# Ivy_Sensor_Shield.net
KiCad netlist of a schematic drawn in EAGLE
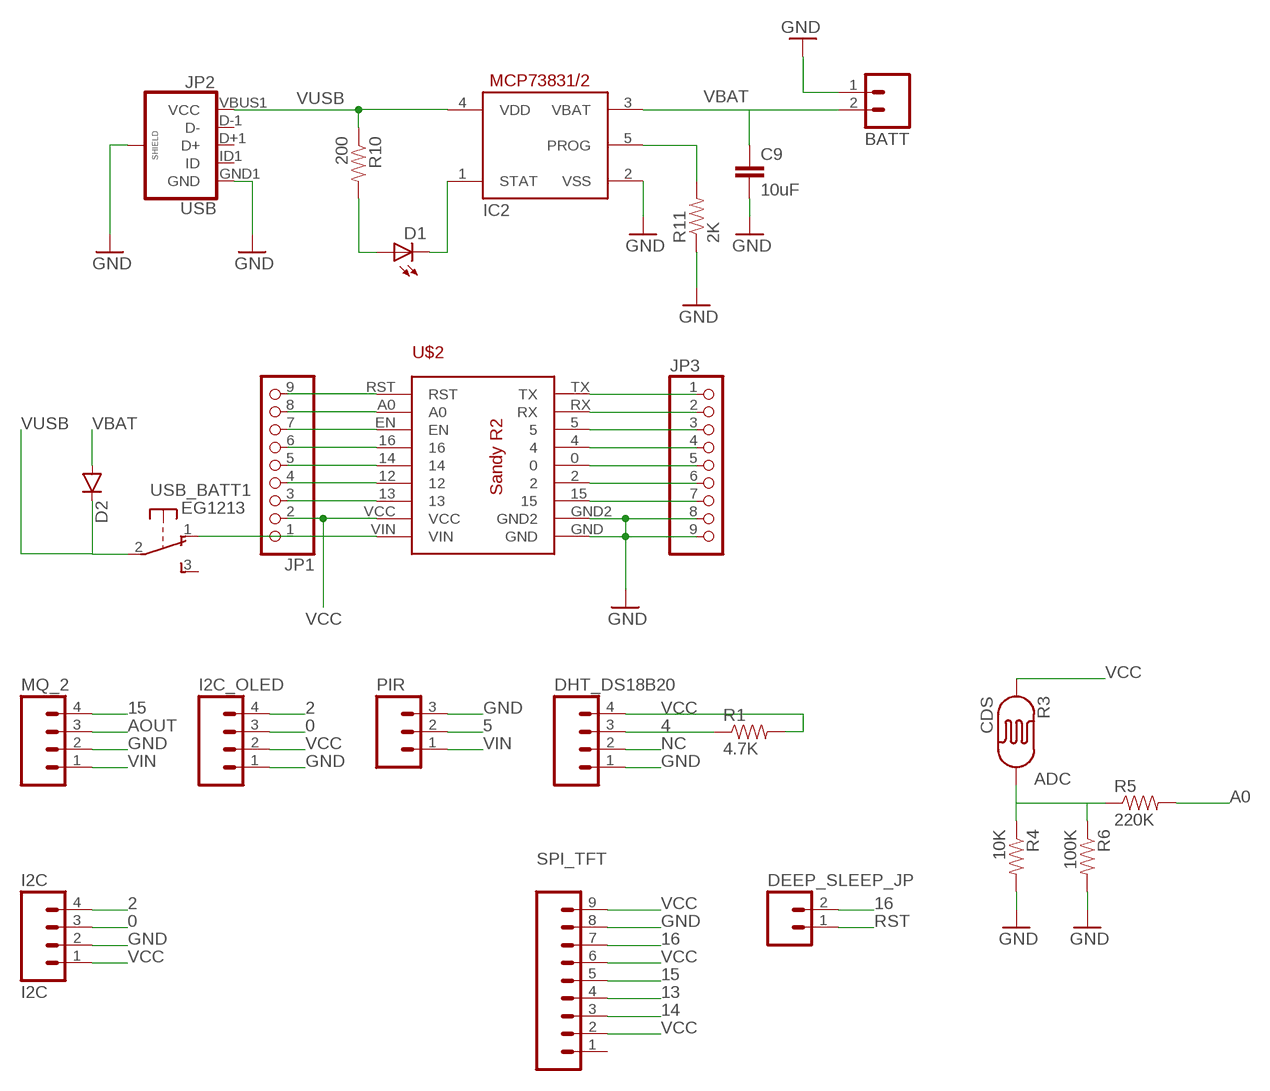
[diagram p0: schematic, sheet 1]

(export (version "E")
  (design (tool "Eeschema 10.0.6"))
  (components
    (comp (ref "BATT")
      (value "M02PTH")
      (footprint "eagle-import:1X02")
      (libsource (lib "eagle-import") (part "M02PTH"))
    )
    (comp (ref "C9")
      (value "10uF")
      (footprint "eagle-import:0805")
      (libsource (lib "eagle-import") (part "CAP0805"))
    )
    (comp (ref "D1")
      (value "LEDCHIPLED_0805")
      (footprint "eagle-import:CHIPLED_0805")
      (libsource (lib "eagle-import") (part "LEDCHIPLED_0805"))
    )
    (comp (ref "D2")
      (value "DIODESOD123")
      (footprint "eagle-import:SOD-123")
      (libsource (lib "eagle-import") (part "DIODESOD123"))
    )
    (comp (ref "DEEP_SLEEP_JP")
      (value "M02PTH")
      (footprint "eagle-import:1X02")
      (libsource (lib "eagle-import") (part "M02PTH"))
    )
    (comp (ref "DHT_DS18B20")
      (value "M04PTH")
      (footprint "eagle-import:1X04")
      (libsource (lib "eagle-import") (part "M04PTH"))
    )
    (comp (ref "I2C")
      (value "I2C")
      (footprint "eagle-import:1X04")
      (libsource (lib "eagle-import") (part "M04PTH"))
    )
    (comp (ref "I2C_OLED")
      (value "M04PTH")
      (footprint "eagle-import:1X04")
      (libsource (lib "eagle-import") (part "M04PTH"))
    )
    (comp (ref "IC2")
      (value "MCP73831/OT")
      (footprint "eagle-import:SOT23-5L")
      (libsource (lib "eagle-import") (part "MCP73831/OT"))
    )
    (comp (ref "JP1")
      (value "PINHD-1X9")
      (footprint "eagle-import:1X09-BIG")
      (libsource (lib "eagle-import") (part "PINHD-1X9"))
    )
    (comp (ref "JP2")
      (value "USB")
      (footprint "eagle-import:USB-B-MICRO-SMD_V03")
      (libsource (lib "eagle-import") (part "USB_MICROB_PLUGCONN-11752"))
    )
    (comp (ref "JP3")
      (value "PINHD-1X9")
      (footprint "eagle-import:1X09-BIG")
      (libsource (lib "eagle-import") (part "PINHD-1X9"))
    )
    (comp (ref "MQ_2")
      (value "M04PTH")
      (footprint "eagle-import:1X04")
      (libsource (lib "eagle-import") (part "M04PTH"))
    )
    (comp (ref "PIR")
      (value "M03PTH")
      (footprint "eagle-import:1X03")
      (libsource (lib "eagle-import") (part "M03PTH"))
    )
    (comp (ref "R1")
      (value "4.7K")
      (footprint "eagle-import:0805")
      (libsource (lib "eagle-import") (part "RESISTOR0805-RES"))
    )
    (comp (ref "R3")
      (value "CDS")
      (footprint "eagle-import:PHOTOCELL_THIN")
      (libsource (lib "eagle-import") (part "PHOTOCELL"))
    )
    (comp (ref "R4")
      (value "10K")
      (footprint "eagle-import:0805")
      (libsource (lib "eagle-import") (part "RESISTOR0805-RES"))
    )
    (comp (ref "R5")
      (value "220K")
      (footprint "eagle-import:0805")
      (libsource (lib "eagle-import") (part "RESISTOR0805-RES"))
    )
    (comp (ref "R6")
      (value "100K")
      (footprint "eagle-import:0805")
      (libsource (lib "eagle-import") (part "RESISTOR0805-RES"))
    )
    (comp (ref "R10")
      (value "200")
      (footprint "eagle-import:0805")
      (libsource (lib "eagle-import") (part "RESISTOR0805-RES"))
    )
    (comp (ref "R11")
      (value "2K")
      (footprint "eagle-import:0805")
      (libsource (lib "eagle-import") (part "RESISTOR0805-RES"))
    )
    (comp (ref "SPI_TFT")
      (value "M09")
      (footprint "eagle-import:1X09")
      (libsource (lib "eagle-import") (part "M09"))
    )
    (comp (ref "U$2")
      (value "MINI-ESPMINI-ESP-LOCK")
      (footprint "eagle-import:MINI-ESP-LOCK")
      (libsource (lib "eagle-import") (part "MINI-ESPMINI-ESP-LOCK"))
    )
    (comp (ref "USB_BATT")
      (value "EG1213")
      (footprint "eagle-import:EG1213")
      (libsource (lib "eagle-import") (part "EG1213"))
    )
  )
  (nets
    (net (code "1") (name "/0") (class "Default")
      (node (ref "I2C") (pin "3") (pinfunction "3_3") (pintype "passive"))
      (node (ref "I2C_OLED") (pin "3") (pinfunction "3_3") (pintype "passive"))
      (node (ref "JP3") (pin "5") (pinfunction "5_5") (pintype "passive"))
      (node (ref "U$2") (pin "0") (pinfunction "0_0") (pintype "bidirectional"))
    )
    (net (code "2") (name "/2") (class "Default")
      (node (ref "I2C") (pin "4") (pinfunction "4_4") (pintype "passive"))
      (node (ref "I2C_OLED") (pin "4") (pinfunction "4_4") (pintype "passive"))
      (node (ref "JP3") (pin "6") (pinfunction "6_6") (pintype "passive"))
      (node (ref "U$2") (pin "2") (pinfunction "2_2") (pintype "bidirectional"))
    )
    (net (code "3") (name "/4") (class "Default")
      (node (ref "DHT_DS18B20") (pin "3") (pinfunction "3_3") (pintype "passive"))
      (node (ref "JP3") (pin "4") (pinfunction "4_4") (pintype "passive"))
      (node (ref "R1") (pin "1") (pinfunction "1_1") (pintype "passive"))
      (node (ref "U$2") (pin "4") (pinfunction "4_4") (pintype "bidirectional"))
    )
    (net (code "4") (name "/5") (class "Default")
      (node (ref "JP3") (pin "3") (pinfunction "3_3") (pintype "passive"))
      (node (ref "PIR") (pin "2") (pinfunction "2_2") (pintype "passive"))
      (node (ref "U$2") (pin "5") (pinfunction "5_5") (pintype "bidirectional"))
    )
    (net (code "5") (name "/13") (class "Default")
      (node (ref "JP1") (pin "3") (pinfunction "3_3") (pintype "passive"))
      (node (ref "SPI_TFT") (pin "4") (pinfunction "4_4") (pintype "passive"))
      (node (ref "U$2") (pin "13") (pinfunction "13_13") (pintype "bidirectional"))
    )
    (net (code "6") (name "/14") (class "Default")
      (node (ref "JP1") (pin "5") (pinfunction "5_5") (pintype "passive"))
      (node (ref "SPI_TFT") (pin "3") (pinfunction "3_3") (pintype "passive"))
      (node (ref "U$2") (pin "14") (pinfunction "14_14") (pintype "bidirectional"))
    )
    (net (code "7") (name "/15") (class "Default")
      (node (ref "JP3") (pin "7") (pinfunction "7_7") (pintype "passive"))
      (node (ref "MQ_2") (pin "4") (pinfunction "4_4") (pintype "passive"))
      (node (ref "SPI_TFT") (pin "5") (pinfunction "5_5") (pintype "passive"))
      (node (ref "U$2") (pin "15") (pinfunction "15_15") (pintype "bidirectional"))
    )
    (net (code "8") (name "/16") (class "Default")
      (node (ref "DEEP_SLEEP_JP") (pin "2") (pinfunction "2_2") (pintype "passive"))
      (node (ref "JP1") (pin "6") (pinfunction "6_6") (pintype "passive"))
      (node (ref "SPI_TFT") (pin "7") (pinfunction "7_7") (pintype "passive"))
      (node (ref "U$2") (pin "16") (pinfunction "16_16") (pintype "bidirectional"))
    )
    (net (code "9") (name "/A0") (class "Default")
      (node (ref "JP1") (pin "8") (pinfunction "8_8") (pintype "passive"))
      (node (ref "R5") (pin "2") (pinfunction "2_2") (pintype "passive"))
      (node (ref "U$2") (pin "A0") (pinfunction "A0_A0") (pintype "bidirectional"))
    )
    (net (code "10") (name "/ADC") (class "Default")
      (node (ref "R3") (pin "2") (pinfunction "P$2_2") (pintype "bidirectional"))
      (node (ref "R4") (pin "1") (pinfunction "1_1") (pintype "passive"))
      (node (ref "R5") (pin "1") (pinfunction "1_1") (pintype "passive"))
      (node (ref "R6") (pin "1") (pinfunction "1_1") (pintype "passive"))
    )
    (net (code "11") (name "/AOUT") (class "Default")
      (node (ref "MQ_2") (pin "3") (pinfunction "3_3") (pintype "passive"))
    )
    (net (code "12") (name "/NC") (class "Default")
      (node (ref "DHT_DS18B20") (pin "2") (pinfunction "2_2") (pintype "passive"))
    )
    (net (code "13") (name "/RST") (class "Default")
      (node (ref "DEEP_SLEEP_JP") (pin "1") (pinfunction "1_1") (pintype "passive"))
      (node (ref "JP1") (pin "9") (pinfunction "9_9") (pintype "passive"))
      (node (ref "U$2") (pin "RST") (pinfunction "RST_RST") (pintype "bidirectional"))
    )
    (net (code "14") (name "/VBAT") (class "Default")
      (node (ref "BATT") (pin "2") (pinfunction "2_2") (pintype "passive"))
      (node (ref "C9") (pin "1") (pinfunction "1_1") (pintype "passive"))
      (node (ref "D2") (pin "A") (pinfunction "A_A") (pintype "passive"))
      (node (ref "IC2") (pin "3") (pinfunction "VBAT_3") (pintype "bidirectional"))
    )
    (net (code "15") (name "/VCC") (class "Default")
      (node (ref "DHT_DS18B20") (pin "4") (pinfunction "4_4") (pintype "passive"))
      (node (ref "I2C") (pin "1") (pinfunction "1_1") (pintype "passive"))
      (node (ref "I2C_OLED") (pin "2") (pinfunction "2_2") (pintype "passive"))
      (node (ref "JP1") (pin "2") (pinfunction "2_2") (pintype "passive"))
      (node (ref "R1") (pin "2") (pinfunction "2_2") (pintype "passive"))
      (node (ref "R3") (pin "1") (pinfunction "P$1_1") (pintype "bidirectional"))
      (node (ref "SPI_TFT") (pin "2") (pinfunction "2_2") (pintype "passive"))
      (node (ref "SPI_TFT") (pin "6") (pinfunction "6_6") (pintype "passive"))
      (node (ref "SPI_TFT") (pin "9") (pinfunction "9_9") (pintype "passive"))
      (node (ref "U$2") (pin "VCC") (pinfunction "VCC_VCC") (pintype "bidirectional"))
    )
    (net (code "16") (name "/VIN") (class "Default")
      (node (ref "JP1") (pin "1") (pinfunction "1_1") (pintype "passive"))
      (node (ref "MQ_2") (pin "1") (pinfunction "1_1") (pintype "passive"))
      (node (ref "PIR") (pin "1") (pinfunction "1_1") (pintype "passive"))
      (node (ref "U$2") (pin "VIN") (pinfunction "VIN_VIN") (pintype "bidirectional"))
      (node (ref "USB_BATT") (pin "1") (pinfunction "O_1") (pintype "passive"))
    )
    (net (code "17") (name "/VUSB") (class "Default")
      (node (ref "D2") (pin "C") (pinfunction "C_C") (pintype "passive"))
      (node (ref "IC2") (pin "4") (pinfunction "VDD_4") (pintype "power_in"))
      (node (ref "JP2") (pin "VBUS1") (pinfunction "VCC_VBUS1") (pintype "bidirectional"))
      (node (ref "R10") (pin "1") (pinfunction "1_1") (pintype "passive"))
      (node (ref "USB_BATT") (pin "2") (pinfunction "P_2") (pintype "passive"))
    )
    (net (code "18") (name "GND") (class "Default")
      (node (ref "BATT") (pin "1") (pinfunction "1_1") (pintype "passive"))
      (node (ref "C9") (pin "2") (pinfunction "2_2") (pintype "passive"))
      (node (ref "DHT_DS18B20") (pin "1") (pinfunction "1_1") (pintype "passive"))
      (node (ref "I2C") (pin "2") (pinfunction "2_2") (pintype "passive"))
      (node (ref "I2C_OLED") (pin "1") (pinfunction "1_1") (pintype "passive"))
      (node (ref "IC2") (pin "2") (pinfunction "VSS_2") (pintype "power_in"))
      (node (ref "JP2") (pin "GND1") (pinfunction "GND_GND1") (pintype "bidirectional"))
      (node (ref "JP2") (pin "SHIELD1") (pinfunction "SHIELD_SHIELD1") (pintype "bidirectional"))
      (node (ref "JP2") (pin "SHIELD2") (pinfunction "SHIELD_SHIELD2") (pintype "bidirectional"))
      (node (ref "JP2") (pin "SHIELD3") (pinfunction "SHIELD_SHIELD3") (pintype "bidirectional"))
      (node (ref "JP3") (pin "8") (pinfunction "8_8") (pintype "passive"))
      (node (ref "JP3") (pin "9") (pinfunction "9_9") (pintype "passive"))
      (node (ref "MQ_2") (pin "2") (pinfunction "2_2") (pintype "passive"))
      (node (ref "PIR") (pin "3") (pinfunction "3_3") (pintype "passive"))
      (node (ref "R11") (pin "1") (pinfunction "1_1") (pintype "passive"))
      (node (ref "R4") (pin "2") (pinfunction "2_2") (pintype "passive"))
      (node (ref "R6") (pin "2") (pinfunction "2_2") (pintype "passive"))
      (node (ref "SPI_TFT") (pin "8") (pinfunction "8_8") (pintype "passive"))
      (node (ref "U$2") (pin "GND") (pinfunction "GND_GND") (pintype "bidirectional"))
      (node (ref "U$2") (pin "GND2") (pinfunction "GND2_GND2") (pintype "bidirectional"))
    )
    (net (code "19") (name "Net-(D1-PadA)") (class "Default")
      (node (ref "D1") (pin "A") (pinfunction "A_A") (pintype "passive"))
      (node (ref "R10") (pin "2") (pinfunction "2_2") (pintype "passive"))
    )
    (net (code "20") (name "Net-(IC2-PROG)") (class "Default")
      (node (ref "IC2") (pin "5") (pinfunction "PROG_5") (pintype "input"))
      (node (ref "R11") (pin "2") (pinfunction "2_2") (pintype "passive"))
    )
    (net (code "21") (name "Net-(IC2-STAT)") (class "Default")
      (node (ref "D1") (pin "C") (pinfunction "C_C") (pintype "passive"))
      (node (ref "IC2") (pin "1") (pinfunction "STAT_1") (pintype "output"))
    )
    (net (code "22") (name "Net-(JP1-Pad4)") (class "Default")
      (node (ref "JP1") (pin "4") (pinfunction "4_4") (pintype "passive"))
      (node (ref "U$2") (pin "12") (pinfunction "12_12") (pintype "bidirectional"))
    )
    (net (code "23") (name "Net-(JP1-Pad7)") (class "Default")
      (node (ref "JP1") (pin "7") (pinfunction "7_7") (pintype "passive"))
      (node (ref "U$2") (pin "EN") (pinfunction "EN_EN") (pintype "bidirectional"))
    )
    (net (code "24") (name "Net-(JP3-Pad1)") (class "Default")
      (node (ref "JP3") (pin "1") (pinfunction "1_1") (pintype "passive"))
      (node (ref "U$2") (pin "TX") (pinfunction "TX_TX") (pintype "bidirectional"))
    )
    (net (code "25") (name "Net-(JP3-Pad2)") (class "Default")
      (node (ref "JP3") (pin "2") (pinfunction "2_2") (pintype "passive"))
      (node (ref "U$2") (pin "RX") (pinfunction "RX_RX") (pintype "bidirectional"))
    )
    (net (code "26") (name "unconnected-(JP2-D+-PadD+1)") (class "Default")
      (node (ref "JP2") (pin "D+1") (pinfunction "D+_D+1") (pintype "bidirectional"))
    )
    (net (code "27") (name "unconnected-(JP2-D--PadD-1)") (class "Default")
      (node (ref "JP2") (pin "D-1") (pinfunction "D-_D-1") (pintype "bidirectional"))
    )
    (net (code "28") (name "unconnected-(JP2-ID-PadID1)") (class "Default")
      (node (ref "JP2") (pin "ID1") (pinfunction "ID_ID1") (pintype "bidirectional"))
    )
    (net (code "29") (name "unconnected-(SPI_TFT-Pad1)") (class "Default")
      (node (ref "SPI_TFT") (pin "1") (pinfunction "1_1") (pintype "passive"))
    )
    (net (code "30") (name "unconnected-(USB_BATTA-S-Pad3)") (class "Default")
      (node (ref "USB_BATT") (pin "3") (pinfunction "S_3") (pintype "passive"))
    )
  )
)
